# Controller.net
KiCad netlist of a schematic drawn in EAGLE
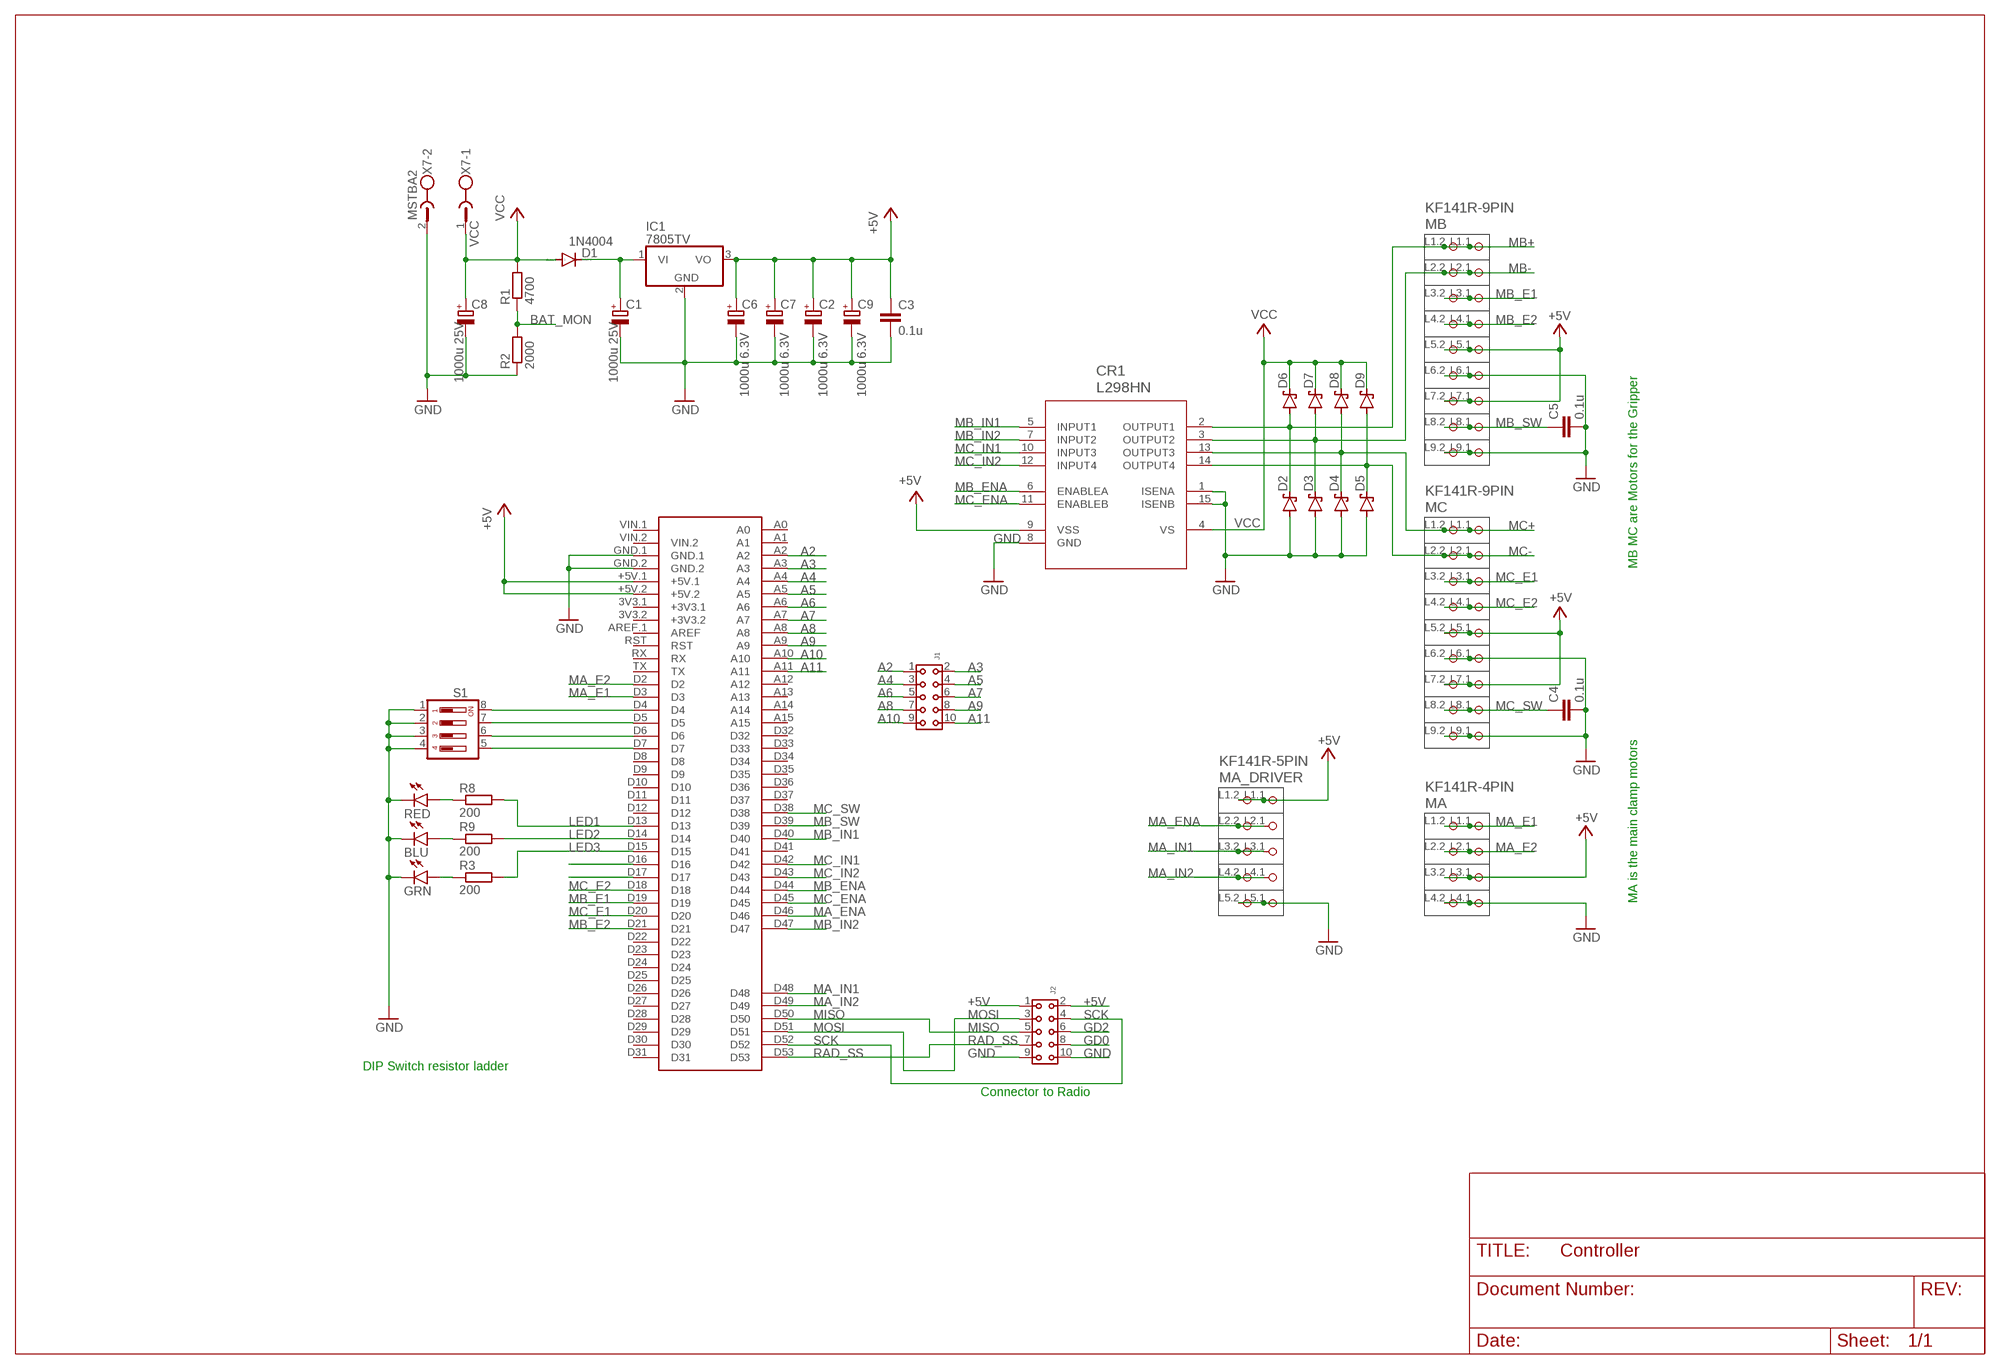
[diagram p0: schematic, sheet 1]

(export (version "E")
  (design (tool "Eeschema 10.0.6"))
  (components
    (comp (ref "BLU")
      (value "LED5MM")
      (footprint "eagle-import:LED5MM")
      (libsource (lib "eagle-import") (part "LED5MM"))
    )
    (comp (ref "C1")
      (value "1000u 25V")
      (footprint "eagle-import:E3,5-10")
      (libsource (lib "eagle-import") (part "resistor_348_CPOL-EUE3.5-10"))
    )
    (comp (ref "C2")
      (value "1000u 6.3V")
      (footprint "eagle-import:E4-8-13HORI")
      (libsource (lib "eagle-import") (part "CPOL-EU"))
    )
    (comp (ref "C3")
      (value "0.1u")
      (footprint "eagle-import:C050-030X075")
      (libsource (lib "eagle-import") (part "C-EU050-030X075"))
    )
    (comp (ref "C4")
      (value "0.1u")
      (footprint "eagle-import:C050-030X075")
      (libsource (lib "eagle-import") (part "C-EU050-030X075"))
    )
    (comp (ref "C5")
      (value "0.1u")
      (footprint "eagle-import:C050-030X075")
      (libsource (lib "eagle-import") (part "C-EU050-030X075"))
    )
    (comp (ref "C6")
      (value "1000u 6.3V")
      (footprint "eagle-import:E4-8-13HORI")
      (libsource (lib "eagle-import") (part "CPOL-EU"))
    )
    (comp (ref "C7")
      (value "1000u 6.3V")
      (footprint "eagle-import:E4-8-13HORI")
      (libsource (lib "eagle-import") (part "CPOL-EU"))
    )
    (comp (ref "C8")
      (value "1000u 25V")
      (footprint "eagle-import:E3,5-10")
      (libsource (lib "eagle-import") (part "resistor_348_CPOL-EUE3.5-10"))
    )
    (comp (ref "C9")
      (value "1000u 6.3V")
      (footprint "eagle-import:E4-8-13HORI")
      (libsource (lib "eagle-import") (part "CPOL-EU"))
    )
    (comp (ref "CR1")
      (value "L298HN")
      (footprint "eagle-import:MULTIWATT15_H_STM")
      (libsource (lib "eagle-import") (part "L298HN"))
    )
    (comp (ref "D1")
      (value "1N4004")
      (footprint "eagle-import:DO41-10")
      (libsource (lib "eagle-import") (part "1N4004"))
    )
    (comp (ref "D2")
      (value "1N5819-B")
      (footprint "eagle-import:DO41-7.6")
      (libsource (lib "eagle-import") (part "1N5819-B"))
    )
    (comp (ref "D3")
      (value "1N5819-B")
      (footprint "eagle-import:DO41-7.6")
      (libsource (lib "eagle-import") (part "1N5819-B"))
    )
    (comp (ref "D4")
      (value "1N5819-B")
      (footprint "eagle-import:DO41-7.6")
      (libsource (lib "eagle-import") (part "1N5819-B"))
    )
    (comp (ref "D5")
      (value "1N5819-B")
      (footprint "eagle-import:DO41-7.6")
      (libsource (lib "eagle-import") (part "1N5819-B"))
    )
    (comp (ref "D6")
      (value "1N5819-B")
      (footprint "eagle-import:DO41-7.6")
      (libsource (lib "eagle-import") (part "1N5819-B"))
    )
    (comp (ref "D7")
      (value "1N5819-B")
      (footprint "eagle-import:DO41-7.6")
      (libsource (lib "eagle-import") (part "1N5819-B"))
    )
    (comp (ref "D8")
      (value "1N5819-B")
      (footprint "eagle-import:DO41-7.6")
      (libsource (lib "eagle-import") (part "1N5819-B"))
    )
    (comp (ref "D9")
      (value "1N5819-B")
      (footprint "eagle-import:DO41-7.6")
      (libsource (lib "eagle-import") (part "1N5819-B"))
    )
    (comp (ref "GRN")
      (value "LED5MM")
      (footprint "eagle-import:LED5MM")
      (libsource (lib "eagle-import") (part "LED5MM"))
    )
    (comp (ref "IC1")
      (value "7805TV")
      (footprint "eagle-import:TO220V")
      (libsource (lib "eagle-import") (part "78TV05"))
    )
    (comp (ref "J1")
      (value "6130XX21821_61301021821")
      (footprint "eagle-import:61301021821")
      (libsource (lib "eagle-import") (part "6130XX21821_61301021821"))
    )
    (comp (ref "J2")
      (value "6130XX21821_61301021821")
      (footprint "eagle-import:61301021821")
      (libsource (lib "eagle-import") (part "6130XX21821_61301021821"))
    )
    (comp (ref "MA")
      (value "KF141R-4PIN")
      (footprint "eagle-import:KF141R-4PIN")
      (libsource (lib "eagle-import") (part "KF141R-4PIN"))
    )
    (comp (ref "MA_DRIVER")
      (value "KF141R-5PIN")
      (footprint "eagle-import:KF141R-5PIN")
      (libsource (lib "eagle-import") (part "KF141R-5PIN"))
    )
    (comp (ref "MB")
      (value "KF141R-9PIN")
      (footprint "eagle-import:KF141R-9PIN")
      (libsource (lib "eagle-import") (part "KF141R-9PIN"))
    )
    (comp (ref "MC")
      (value "KF141R-9PIN")
      (footprint "eagle-import:KF141R-9PIN")
      (libsource (lib "eagle-import") (part "KF141R-9PIN"))
    )
    (comp (ref "R1")
      (value "4700")
      (footprint "eagle-import:0207_7")
      (libsource (lib "eagle-import") (part "R-EU_0207/7"))
    )
    (comp (ref "R2")
      (value "2000")
      (footprint "eagle-import:0207_7")
      (libsource (lib "eagle-import") (part "R-EU_0207/7"))
    )
    (comp (ref "R3")
      (value "200")
      (footprint "eagle-import:0207_7")
      (libsource (lib "eagle-import") (part "R-EU_0207/7"))
    )
    (comp (ref "R8")
      (value "200")
      (footprint "eagle-import:0207_7")
      (libsource (lib "eagle-import") (part "R-EU_0207/7"))
    )
    (comp (ref "R9")
      (value "200")
      (footprint "eagle-import:0207_7")
      (libsource (lib "eagle-import") (part "R-EU_0207/7"))
    )
    (comp (ref "RED")
      (value "LED5MM")
      (footprint "eagle-import:LED5MM")
      (libsource (lib "eagle-import") (part "LED5MM"))
    )
    (comp (ref "S1")
      (value "DIP04YL")
      (footprint "eagle-import:DIP04YL")
      (libsource (lib "eagle-import") (part "DIP04YL"))
    )
    (comp (ref "U$1")
      (value "MEGA2560_MIKRO")
      (footprint "eagle-import:MEGA2560_MIKRO")
      (libsource (lib "eagle-import") (part "MEGA2560_MIKRO"))
    )
    (comp (ref "X7")
      (value "MSTBA2")
      (footprint "eagle-import:MSTBA2")
      (fields (field (name "MF") "FARNELL") (field (name "MPN") "1757242"))
      (libsource (lib "eagle-import") (part "MSTBA2"))
    )
  )
  (nets
    (net (code "1") (name "+5V") (class "Default")
      (node (ref "C2") (pin "+") (pinfunction "+_+") (pintype "passive"))
      (node (ref "C3") (pin "1") (pinfunction "1_1") (pintype "passive"))
      (node (ref "C6") (pin "+") (pinfunction "+_+") (pintype "passive"))
      (node (ref "C7") (pin "+") (pinfunction "+_+") (pintype "passive"))
      (node (ref "C9") (pin "+") (pinfunction "+_+") (pintype "passive"))
      (node (ref "CR1") (pin "9") (pinfunction "VSS_9") (pintype "power_in"))
      (node (ref "IC1") (pin "3") (pinfunction "VO_3") (pintype "passive"))
      (node (ref "J2") (pin "1") (pinfunction "1_1") (pintype "passive"))
      (node (ref "J2") (pin "2") (pinfunction "2_2") (pintype "passive"))
      (node (ref "MA") (pin "L3.1") (pinfunction "P3.1_L3.1") (pintype "bidirectional"))
      (node (ref "MA") (pin "L3.2") (pinfunction "P3.2_L3.2") (pintype "bidirectional"))
      (node (ref "MA_DRIVER") (pin "L1.1") (pinfunction "P1.1_L1.1") (pintype "bidirectional"))
      (node (ref "MA_DRIVER") (pin "L1.2") (pinfunction "P1.2_L1.2") (pintype "bidirectional"))
      (node (ref "MB") (pin "L5.1") (pinfunction "P5.1_L5.1") (pintype "bidirectional"))
      (node (ref "MB") (pin "L5.2") (pinfunction "P5.2_L5.2") (pintype "bidirectional"))
      (node (ref "MB") (pin "L7.1") (pinfunction "P7.1_L7.1") (pintype "bidirectional"))
      (node (ref "MB") (pin "L7.2") (pinfunction "P7.2_L7.2") (pintype "bidirectional"))
      (node (ref "MC") (pin "L5.1") (pinfunction "P5.1_L5.1") (pintype "bidirectional"))
      (node (ref "MC") (pin "L5.2") (pinfunction "P5.2_L5.2") (pintype "bidirectional"))
      (node (ref "MC") (pin "L7.1") (pinfunction "P7.1_L7.1") (pintype "bidirectional"))
      (node (ref "MC") (pin "L7.2") (pinfunction "P7.2_L7.2") (pintype "bidirectional"))
      (node (ref "U$1") (pin "+5V.1") (pinfunction "+5V.1_+5V.1") (pintype "bidirectional"))
      (node (ref "U$1") (pin "+5V.2") (pinfunction "+5V.2_+5V.2") (pintype "bidirectional"))
    )
    (net (code "2") (name "/A2") (class "Default")
      (node (ref "J1") (pin "1") (pinfunction "1_1") (pintype "passive"))
      (node (ref "U$1") (pin "A2") (pinfunction "A2_A2") (pintype "bidirectional"))
    )
    (net (code "3") (name "/A3") (class "Default")
      (node (ref "J1") (pin "2") (pinfunction "2_2") (pintype "passive"))
      (node (ref "U$1") (pin "A3") (pinfunction "A3_A3") (pintype "bidirectional"))
    )
    (net (code "4") (name "/A4") (class "Default")
      (node (ref "J1") (pin "3") (pinfunction "3_3") (pintype "passive"))
      (node (ref "U$1") (pin "A4") (pinfunction "A4_A4") (pintype "bidirectional"))
    )
    (net (code "5") (name "/A5") (class "Default")
      (node (ref "J1") (pin "4") (pinfunction "4_4") (pintype "passive"))
      (node (ref "U$1") (pin "A5") (pinfunction "A5_A5") (pintype "bidirectional"))
    )
    (net (code "6") (name "/A6") (class "Default")
      (node (ref "J1") (pin "5") (pinfunction "5_5") (pintype "passive"))
      (node (ref "U$1") (pin "A6") (pinfunction "A6_A6") (pintype "bidirectional"))
    )
    (net (code "7") (name "/A7") (class "Default")
      (node (ref "J1") (pin "6") (pinfunction "6_6") (pintype "passive"))
      (node (ref "U$1") (pin "A7") (pinfunction "A7_A7") (pintype "bidirectional"))
    )
    (net (code "8") (name "/A8") (class "Default")
      (node (ref "J1") (pin "7") (pinfunction "7_7") (pintype "passive"))
      (node (ref "U$1") (pin "A8") (pinfunction "A8_A8") (pintype "bidirectional"))
    )
    (net (code "9") (name "/A9") (class "Default")
      (node (ref "J1") (pin "8") (pinfunction "8_8") (pintype "passive"))
      (node (ref "U$1") (pin "A9") (pinfunction "A9_A9") (pintype "bidirectional"))
    )
    (net (code "10") (name "/A10") (class "Default")
      (node (ref "J1") (pin "9") (pinfunction "9_9") (pintype "passive"))
      (node (ref "U$1") (pin "A10") (pinfunction "A10_A10") (pintype "bidirectional"))
    )
    (net (code "11") (name "/A11") (class "Default")
      (node (ref "J1") (pin "10") (pinfunction "10_10") (pintype "passive"))
      (node (ref "U$1") (pin "A11") (pinfunction "A11_A11") (pintype "bidirectional"))
    )
    (net (code "12") (name "/BAT_MON") (class "Default")
      (node (ref "R1") (pin "1") (pinfunction "1_1") (pintype "passive"))
      (node (ref "R2") (pin "2") (pinfunction "2_2") (pintype "passive"))
    )
    (net (code "13") (name "/GD0") (class "Default")
      (node (ref "J2") (pin "8") (pinfunction "8_8") (pintype "passive"))
    )
    (net (code "14") (name "/GD2") (class "Default")
      (node (ref "J2") (pin "6") (pinfunction "6_6") (pintype "passive"))
    )
    (net (code "15") (name "/LED1") (class "Default")
      (node (ref "R8") (pin "2") (pinfunction "2_2") (pintype "passive"))
      (node (ref "U$1") (pin "D13") (pinfunction "D13_D13") (pintype "bidirectional"))
    )
    (net (code "16") (name "/LED2") (class "Default")
      (node (ref "R9") (pin "2") (pinfunction "2_2") (pintype "passive"))
      (node (ref "U$1") (pin "D14") (pinfunction "D14_D14") (pintype "bidirectional"))
    )
    (net (code "17") (name "/LED3") (class "Default")
      (node (ref "R3") (pin "2") (pinfunction "2_2") (pintype "passive"))
      (node (ref "U$1") (pin "D15") (pinfunction "D15_D15") (pintype "bidirectional"))
    )
    (net (code "18") (name "/MA_E1") (class "Default")
      (node (ref "MA") (pin "L1.1") (pinfunction "P1.1_L1.1") (pintype "bidirectional"))
      (node (ref "MA") (pin "L1.2") (pinfunction "P1.2_L1.2") (pintype "bidirectional"))
      (node (ref "U$1") (pin "D3") (pinfunction "D3_D3") (pintype "bidirectional"))
    )
    (net (code "19") (name "/MA_E2") (class "Default")
      (node (ref "MA") (pin "L2.1") (pinfunction "P2.1_L2.1") (pintype "bidirectional"))
      (node (ref "MA") (pin "L2.2") (pinfunction "P2.2_L2.2") (pintype "bidirectional"))
      (node (ref "U$1") (pin "D2") (pinfunction "D2_D2") (pintype "bidirectional"))
    )
    (net (code "20") (name "/MA_ENA") (class "Default")
      (node (ref "MA_DRIVER") (pin "L2.1") (pinfunction "P2.1_L2.1") (pintype "bidirectional"))
      (node (ref "MA_DRIVER") (pin "L2.2") (pinfunction "P2.2_L2.2") (pintype "bidirectional"))
      (node (ref "U$1") (pin "D46") (pinfunction "D46_D46") (pintype "bidirectional"))
    )
    (net (code "21") (name "/MA_IN1") (class "Default")
      (node (ref "MA_DRIVER") (pin "L3.1") (pinfunction "P3.1_L3.1") (pintype "bidirectional"))
      (node (ref "MA_DRIVER") (pin "L3.2") (pinfunction "P3.2_L3.2") (pintype "bidirectional"))
      (node (ref "U$1") (pin "D48") (pinfunction "D48_D48") (pintype "bidirectional"))
    )
    (net (code "22") (name "/MA_IN2") (class "Default")
      (node (ref "MA_DRIVER") (pin "L4.1") (pinfunction "P4.1_L4.1") (pintype "bidirectional"))
      (node (ref "MA_DRIVER") (pin "L4.2") (pinfunction "P4.2_L4.2") (pintype "bidirectional"))
      (node (ref "U$1") (pin "D49") (pinfunction "D49_D49") (pintype "bidirectional"))
    )
    (net (code "23") (name "/MB+") (class "Default")
      (node (ref "CR1") (pin "2") (pinfunction "OUTPUT1_2") (pintype "output"))
      (node (ref "D2") (pin "C") (pinfunction "C_C") (pintype "passive"))
      (node (ref "D6") (pin "A") (pinfunction "A_A") (pintype "passive"))
      (node (ref "MB") (pin "L1.1") (pinfunction "P1.1_L1.1") (pintype "bidirectional"))
      (node (ref "MB") (pin "L1.2") (pinfunction "P1.2_L1.2") (pintype "bidirectional"))
    )
    (net (code "24") (name "/MB-") (class "Default")
      (node (ref "CR1") (pin "3") (pinfunction "OUTPUT2_3") (pintype "output"))
      (node (ref "D3") (pin "C") (pinfunction "C_C") (pintype "passive"))
      (node (ref "D7") (pin "A") (pinfunction "A_A") (pintype "passive"))
      (node (ref "MB") (pin "L2.1") (pinfunction "P2.1_L2.1") (pintype "bidirectional"))
      (node (ref "MB") (pin "L2.2") (pinfunction "P2.2_L2.2") (pintype "bidirectional"))
    )
    (net (code "25") (name "/MB_E1") (class "Default")
      (node (ref "MB") (pin "L3.1") (pinfunction "P3.1_L3.1") (pintype "bidirectional"))
      (node (ref "MB") (pin "L3.2") (pinfunction "P3.2_L3.2") (pintype "bidirectional"))
      (node (ref "U$1") (pin "D19") (pinfunction "D19_D19") (pintype "bidirectional"))
    )
    (net (code "26") (name "/MB_E2") (class "Default")
      (node (ref "MB") (pin "L4.1") (pinfunction "P4.1_L4.1") (pintype "bidirectional"))
      (node (ref "MB") (pin "L4.2") (pinfunction "P4.2_L4.2") (pintype "bidirectional"))
      (node (ref "U$1") (pin "D21") (pinfunction "D21_D21") (pintype "bidirectional"))
    )
    (net (code "27") (name "/MB_ENA") (class "Default")
      (node (ref "CR1") (pin "6") (pinfunction "ENABLEA_6") (pintype "input"))
      (node (ref "U$1") (pin "D44") (pinfunction "D44_D44") (pintype "bidirectional"))
    )
    (net (code "28") (name "/MB_IN1") (class "Default")
      (node (ref "CR1") (pin "5") (pinfunction "INPUT1_5") (pintype "input"))
      (node (ref "U$1") (pin "D40") (pinfunction "D40_D40") (pintype "bidirectional"))
    )
    (net (code "29") (name "/MB_IN2") (class "Default")
      (node (ref "CR1") (pin "7") (pinfunction "INPUT2_7") (pintype "input"))
      (node (ref "U$1") (pin "D47") (pinfunction "D47_D47") (pintype "bidirectional"))
    )
    (net (code "30") (name "/MB_SW") (class "Default")
      (node (ref "C5") (pin "1") (pinfunction "1_1") (pintype "passive"))
      (node (ref "MB") (pin "L8.1") (pinfunction "P8.1_L8.1") (pintype "bidirectional"))
      (node (ref "MB") (pin "L8.2") (pinfunction "P8.2_L8.2") (pintype "bidirectional"))
      (node (ref "U$1") (pin "D39") (pinfunction "D39_D39") (pintype "bidirectional"))
    )
    (net (code "31") (name "/MC+") (class "Default")
      (node (ref "CR1") (pin "13") (pinfunction "OUTPUT3_13") (pintype "output"))
      (node (ref "D4") (pin "C") (pinfunction "C_C") (pintype "passive"))
      (node (ref "D8") (pin "A") (pinfunction "A_A") (pintype "passive"))
      (node (ref "MC") (pin "L1.1") (pinfunction "P1.1_L1.1") (pintype "bidirectional"))
      (node (ref "MC") (pin "L1.2") (pinfunction "P1.2_L1.2") (pintype "bidirectional"))
    )
    (net (code "32") (name "/MC-") (class "Default")
      (node (ref "CR1") (pin "14") (pinfunction "OUTPUT4_14") (pintype "output"))
      (node (ref "D5") (pin "C") (pinfunction "C_C") (pintype "passive"))
      (node (ref "D9") (pin "A") (pinfunction "A_A") (pintype "passive"))
      (node (ref "MC") (pin "L2.1") (pinfunction "P2.1_L2.1") (pintype "bidirectional"))
      (node (ref "MC") (pin "L2.2") (pinfunction "P2.2_L2.2") (pintype "bidirectional"))
    )
    (net (code "33") (name "/MC_E1") (class "Default")
      (node (ref "MC") (pin "L3.1") (pinfunction "P3.1_L3.1") (pintype "bidirectional"))
      (node (ref "MC") (pin "L3.2") (pinfunction "P3.2_L3.2") (pintype "bidirectional"))
      (node (ref "U$1") (pin "D20") (pinfunction "D20_D20") (pintype "bidirectional"))
    )
    (net (code "34") (name "/MC_E2") (class "Default")
      (node (ref "MC") (pin "L4.1") (pinfunction "P4.1_L4.1") (pintype "bidirectional"))
      (node (ref "MC") (pin "L4.2") (pinfunction "P4.2_L4.2") (pintype "bidirectional"))
      (node (ref "U$1") (pin "D18") (pinfunction "D18_D18") (pintype "bidirectional"))
    )
    (net (code "35") (name "/MC_ENA") (class "Default")
      (node (ref "CR1") (pin "11") (pinfunction "ENABLEB_11") (pintype "input"))
      (node (ref "U$1") (pin "D45") (pinfunction "D45_D45") (pintype "bidirectional"))
    )
    (net (code "36") (name "/MC_IN1") (class "Default")
      (node (ref "CR1") (pin "10") (pinfunction "INPUT3_10") (pintype "input"))
      (node (ref "U$1") (pin "D42") (pinfunction "D42_D42") (pintype "bidirectional"))
    )
    (net (code "37") (name "/MC_IN2") (class "Default")
      (node (ref "CR1") (pin "12") (pinfunction "INPUT4_12") (pintype "input"))
      (node (ref "U$1") (pin "D43") (pinfunction "D43_D43") (pintype "bidirectional"))
    )
    (net (code "38") (name "/MC_SW") (class "Default")
      (node (ref "C4") (pin "1") (pinfunction "1_1") (pintype "passive"))
      (node (ref "MC") (pin "L8.1") (pinfunction "P8.1_L8.1") (pintype "bidirectional"))
      (node (ref "MC") (pin "L8.2") (pinfunction "P8.2_L8.2") (pintype "bidirectional"))
      (node (ref "U$1") (pin "D38") (pinfunction "D38_D38") (pintype "bidirectional"))
    )
    (net (code "39") (name "/MISO") (class "Default")
      (node (ref "J2") (pin "5") (pinfunction "5_5") (pintype "passive"))
      (node (ref "U$1") (pin "D50") (pinfunction "D50_D50") (pintype "bidirectional"))
    )
    (net (code "40") (name "/MOSI") (class "Default")
      (node (ref "J2") (pin "3") (pinfunction "3_3") (pintype "passive"))
      (node (ref "U$1") (pin "D51") (pinfunction "D51_D51") (pintype "bidirectional"))
    )
    (net (code "41") (name "/RAD_SS") (class "Default")
      (node (ref "J2") (pin "7") (pinfunction "7_7") (pintype "passive"))
      (node (ref "U$1") (pin "D53") (pinfunction "D53_D53") (pintype "bidirectional"))
    )
    (net (code "42") (name "/SCK") (class "Default")
      (node (ref "J2") (pin "4") (pinfunction "4_4") (pintype "passive"))
      (node (ref "U$1") (pin "D52") (pinfunction "D52_D52") (pintype "bidirectional"))
    )
    (net (code "43") (name "GND") (class "Default")
      (node (ref "BLU") (pin "K") (pinfunction "C_K") (pintype "passive"))
      (node (ref "C1") (pin "-") (pinfunction "-_-") (pintype "passive"))
      (node (ref "C2") (pin "-") (pinfunction "-_-") (pintype "passive"))
      (node (ref "C3") (pin "2") (pinfunction "2_2") (pintype "passive"))
      (node (ref "C4") (pin "2") (pinfunction "2_2") (pintype "passive"))
      (node (ref "C5") (pin "2") (pinfunction "2_2") (pintype "passive"))
      (node (ref "C6") (pin "-") (pinfunction "-_-") (pintype "passive"))
      (node (ref "C7") (pin "-") (pinfunction "-_-") (pintype "passive"))
      (node (ref "C8") (pin "-") (pinfunction "-_-") (pintype "passive"))
      (node (ref "C9") (pin "-") (pinfunction "-_-") (pintype "passive"))
      (node (ref "CR1") (pin "1") (pinfunction "ISENA_1") (pintype "passive"))
      (node (ref "CR1") (pin "15") (pinfunction "ISENB_15") (pintype "passive"))
      (node (ref "CR1") (pin "8") (pinfunction "GND_8") (pintype "power_in"))
      (node (ref "D2") (pin "A") (pinfunction "A_A") (pintype "passive"))
      (node (ref "D3") (pin "A") (pinfunction "A_A") (pintype "passive"))
      (node (ref "D4") (pin "A") (pinfunction "A_A") (pintype "passive"))
      (node (ref "D5") (pin "A") (pinfunction "A_A") (pintype "passive"))
      (node (ref "GRN") (pin "K") (pinfunction "C_K") (pintype "passive"))
      (node (ref "IC1") (pin "2") (pinfunction "GND_2") (pintype "passive"))
      (node (ref "J2") (pin "10") (pinfunction "10_10") (pintype "passive"))
      (node (ref "J2") (pin "9") (pinfunction "9_9") (pintype "passive"))
      (node (ref "MA") (pin "L4.1") (pinfunction "P4.1_L4.1") (pintype "bidirectional"))
      (node (ref "MA") (pin "L4.2") (pinfunction "P4.2_L4.2") (pintype "bidirectional"))
      (node (ref "MA_DRIVER") (pin "L5.1") (pinfunction "P5.1_L5.1") (pintype "bidirectional"))
      (node (ref "MA_DRIVER") (pin "L5.2") (pinfunction "P5.2_L5.2") (pintype "bidirectional"))
      (node (ref "MB") (pin "L6.1") (pinfunction "P6.1_L6.1") (pintype "bidirectional"))
      (node (ref "MB") (pin "L6.2") (pinfunction "P6.2_L6.2") (pintype "bidirectional"))
      (node (ref "MB") (pin "L9.1") (pinfunction "P9.1_L9.1") (pintype "bidirectional"))
      (node (ref "MB") (pin "L9.2") (pinfunction "P9.2_L9.2") (pintype "bidirectional"))
      (node (ref "MC") (pin "L6.1") (pinfunction "P6.1_L6.1") (pintype "bidirectional"))
      (node (ref "MC") (pin "L6.2") (pinfunction "P6.2_L6.2") (pintype "bidirectional"))
      (node (ref "MC") (pin "L9.1") (pinfunction "P9.1_L9.1") (pintype "bidirectional"))
      (node (ref "MC") (pin "L9.2") (pinfunction "P9.2_L9.2") (pintype "bidirectional"))
      (node (ref "R2") (pin "1") (pinfunction "1_1") (pintype "passive"))
      (node (ref "RED") (pin "K") (pinfunction "C_K") (pintype "passive"))
      (node (ref "S1") (pin "1") (pinfunction "1_1") (pintype "passive"))
      (node (ref "S1") (pin "2") (pinfunction "2_2") (pintype "passive"))
      (node (ref "S1") (pin "3") (pinfunction "3_3") (pintype "passive"))
      (node (ref "S1") (pin "4") (pinfunction "4_4") (pintype "passive"))
      (node (ref "U$1") (pin "GND.1") (pinfunction "GND.1_GND.1") (pintype "bidirectional"))
      (node (ref "U$1") (pin "GND.2") (pinfunction "GND.2_GND.2") (pintype "bidirectional"))
      (node (ref "X7") (pin "2") (pinfunction "1_2") (pintype "passive"))
    )
    (net (code "44") (name "Net-(BLU-PadA)") (class "Default")
      (node (ref "BLU") (pin "A") (pinfunction "A_A") (pintype "passive"))
      (node (ref "R9") (pin "1") (pinfunction "1_1") (pintype "passive"))
    )
    (net (code "45") (name "Net-(GRN-PadA)") (class "Default")
      (node (ref "GRN") (pin "A") (pinfunction "A_A") (pintype "passive"))
      (node (ref "R3") (pin "1") (pinfunction "1_1") (pintype "passive"))
    )
    (net (code "46") (name "Net-(IC1-VI)") (class "Default")
      (node (ref "C1") (pin "+") (pinfunction "+_+") (pintype "passive"))
      (node (ref "D1") (pin "C") (pinfunction "C_C") (pintype "passive"))
      (node (ref "IC1") (pin "1") (pinfunction "VI_1") (pintype "input"))
    )
    (net (code "47") (name "Net-(R8-Pad1)") (class "Default")
      (node (ref "R8") (pin "1") (pinfunction "1_1") (pintype "passive"))
      (node (ref "RED") (pin "A") (pinfunction "A_A") (pintype "passive"))
    )
    (net (code "48") (name "Net-(S1-Pad5)") (class "Default")
      (node (ref "S1") (pin "5") (pinfunction "5_5") (pintype "passive"))
      (node (ref "U$1") (pin "D7") (pinfunction "D7_D7") (pintype "bidirectional"))
    )
    (net (code "49") (name "Net-(S1-Pad6)") (class "Default")
      (node (ref "S1") (pin "6") (pinfunction "6_6") (pintype "passive"))
      (node (ref "U$1") (pin "D6") (pinfunction "D6_D6") (pintype "bidirectional"))
    )
    (net (code "50") (name "Net-(S1-Pad7)") (class "Default")
      (node (ref "S1") (pin "7") (pinfunction "7_7") (pintype "passive"))
      (node (ref "U$1") (pin "D5") (pinfunction "D5_D5") (pintype "bidirectional"))
    )
    (net (code "51") (name "Net-(S1-Pad8)") (class "Default")
      (node (ref "S1") (pin "8") (pinfunction "8_8") (pintype "passive"))
      (node (ref "U$1") (pin "D4") (pinfunction "D4_D4") (pintype "bidirectional"))
    )
    (net (code "52") (name "VCC") (class "Default")
      (node (ref "C8") (pin "+") (pinfunction "+_+") (pintype "passive"))
      (node (ref "CR1") (pin "4") (pinfunction "VS_4") (pintype "power_in"))
      (node (ref "D1") (pin "A") (pinfunction "A_A") (pintype "passive"))
      (node (ref "D6") (pin "C") (pinfunction "C_C") (pintype "passive"))
      (node (ref "D7") (pin "C") (pinfunction "C_C") (pintype "passive"))
      (node (ref "D8") (pin "C") (pinfunction "C_C") (pintype "passive"))
      (node (ref "D9") (pin "C") (pinfunction "C_C") (pintype "passive"))
      (node (ref "R1") (pin "2") (pinfunction "2_2") (pintype "passive"))
      (node (ref "X7") (pin "1") (pinfunction "1_1") (pintype "passive"))
    )
    (net (code "53") (name "unconnected-(U$1-+3V3.1-Pad3V3.1)") (class "Default")
      (node (ref "U$1") (pin "3V3.1") (pinfunction "+3V3.1_3V3.1") (pintype "bidirectional"))
    )
    (net (code "54") (name "unconnected-(U$1-+3V3.2-Pad3V3.2)") (class "Default")
      (node (ref "U$1") (pin "3V3.2") (pinfunction "+3V3.2_3V3.2") (pintype "bidirectional"))
    )
    (net (code "55") (name "unconnected-(U$1-AREF-PadAREF.1)") (class "Default")
      (node (ref "U$1") (pin "AREF.1") (pinfunction "AREF_AREF.1") (pintype "bidirectional"))
    )
    (net (code "56") (name "unconnected-(U$1-PadA0)") (class "Default")
      (node (ref "U$1") (pin "A0") (pinfunction "A0_A0") (pintype "bidirectional"))
    )
    (net (code "57") (name "unconnected-(U$1-PadA1)") (class "Default")
      (node (ref "U$1") (pin "A1") (pinfunction "A1_A1") (pintype "bidirectional"))
    )
    (net (code "58") (name "unconnected-(U$1-PadA12)") (class "Default")
      (node (ref "U$1") (pin "A12") (pinfunction "A12_A12") (pintype "bidirectional"))
    )
    (net (code "59") (name "unconnected-(U$1-PadA13)") (class "Default")
      (node (ref "U$1") (pin "A13") (pinfunction "A13_A13") (pintype "bidirectional"))
    )
    (net (code "60") (name "unconnected-(U$1-PadA14)") (class "Default")
      (node (ref "U$1") (pin "A14") (pinfunction "A14_A14") (pintype "bidirectional"))
    )
    (net (code "61") (name "unconnected-(U$1-PadA15)") (class "Default")
      (node (ref "U$1") (pin "A15") (pinfunction "A15_A15") (pintype "bidirectional"))
    )
    (net (code "62") (name "unconnected-(U$1-PadD8)") (class "Default")
      (node (ref "U$1") (pin "D8") (pinfunction "D8_D8") (pintype "bidirectional"))
    )
    (net (code "63") (name "unconnected-(U$1-PadD9)") (class "Default")
      (node (ref "U$1") (pin "D9") (pinfunction "D9_D9") (pintype "bidirectional"))
    )
    (net (code "64") (name "unconnected-(U$1-PadD10)") (class "Default")
      (node (ref "U$1") (pin "D10") (pinfunction "D10_D10") (pintype "bidirectional"))
    )
    (net (code "65") (name "unconnected-(U$1-PadD11)") (class "Default")
      (node (ref "U$1") (pin "D11") (pinfunction "D11_D11") (pintype "bidirectional"))
    )
    (net (code "66") (name "unconnected-(U$1-PadD12)") (class "Default")
      (node (ref "U$1") (pin "D12") (pinfunction "D12_D12") (pintype "bidirectional"))
    )
    (net (code "67") (name "unconnected-(U$1-PadD16)") (class "Default")
      (node (ref "U$1") (pin "D16") (pinfunction "D16_D16") (pintype "bidirectional"))
    )
    (net (code "68") (name "unconnected-(U$1-PadD17)") (class "Default")
      (node (ref "U$1") (pin "D17") (pinfunction "D17_D17") (pintype "bidirectional"))
    )
    (net (code "69") (name "unconnected-(U$1-PadD22)") (class "Default")
      (node (ref "U$1") (pin "D22") (pinfunction "D22_D22") (pintype "bidirectional"))
    )
    (net (code "70") (name "unconnected-(U$1-PadD23)") (class "Default")
      (node (ref "U$1") (pin "D23") (pinfunction "D23_D23") (pintype "bidirectional"))
    )
    (net (code "71") (name "unconnected-(U$1-PadD24)") (class "Default")
      (node (ref "U$1") (pin "D24") (pinfunction "D24_D24") (pintype "bidirectional"))
    )
    (net (code "72") (name "unconnected-(U$1-PadD25)") (class "Default")
      (node (ref "U$1") (pin "D25") (pinfunction "D25_D25") (pintype "bidirectional"))
    )
    (net (code "73") (name "unconnected-(U$1-PadD26)") (class "Default")
      (node (ref "U$1") (pin "D26") (pinfunction "D26_D26") (pintype "bidirectional"))
    )
    (net (code "74") (name "unconnected-(U$1-PadD27)") (class "Default")
      (node (ref "U$1") (pin "D27") (pinfunction "D27_D27") (pintype "bidirectional"))
    )
    (net (code "75") (name "unconnected-(U$1-PadD28)") (class "Default")
      (node (ref "U$1") (pin "D28") (pinfunction "D28_D28") (pintype "bidirectional"))
    )
    (net (code "76") (name "unconnected-(U$1-PadD29)") (class "Default")
      (node (ref "U$1") (pin "D29") (pinfunction "D29_D29") (pintype "bidirectional"))
    )
    (net (code "77") (name "unconnected-(U$1-PadD30)") (class "Default")
      (node (ref "U$1") (pin "D30") (pinfunction "D30_D30") (pintype "bidirectional"))
    )
    (net (code "78") (name "unconnected-(U$1-PadD31)") (class "Default")
      (node (ref "U$1") (pin "D31") (pinfunction "D31_D31") (pintype "bidirectional"))
    )
    (net (code "79") (name "unconnected-(U$1-PadD32)") (class "Default")
      (node (ref "U$1") (pin "D32") (pinfunction "D32_D32") (pintype "bidirectional"))
    )
    (net (code "80") (name "unconnected-(U$1-PadD33)") (class "Default")
      (node (ref "U$1") (pin "D33") (pinfunction "D33_D33") (pintype "bidirectional"))
    )
    (net (code "81") (name "unconnected-(U$1-PadD34)") (class "Default")
      (node (ref "U$1") (pin "D34") (pinfunction "D34_D34") (pintype "bidirectional"))
    )
    (net (code "82") (name "unconnected-(U$1-PadD35)") (class "Default")
      (node (ref "U$1") (pin "D35") (pinfunction "D35_D35") (pintype "bidirectional"))
    )
    (net (code "83") (name "unconnected-(U$1-PadD36)") (class "Default")
      (node (ref "U$1") (pin "D36") (pinfunction "D36_D36") (pintype "bidirectional"))
    )
    (net (code "84") (name "unconnected-(U$1-PadD37)") (class "Default")
      (node (ref "U$1") (pin "D37") (pinfunction "D37_D37") (pintype "bidirectional"))
    )
    (net (code "85") (name "unconnected-(U$1-PadD41)") (class "Default")
      (node (ref "U$1") (pin "D41") (pinfunction "D41_D41") (pintype "bidirectional"))
    )
    (net (code "86") (name "unconnected-(U$1-PadRST)") (class "Default")
      (node (ref "U$1") (pin "RST") (pinfunction "RST_RST") (pintype "bidirectional"))
    )
    (net (code "87") (name "unconnected-(U$1-PadRX)") (class "Default")
      (node (ref "U$1") (pin "RX") (pinfunction "RX_RX") (pintype "bidirectional"))
    )
    (net (code "88") (name "unconnected-(U$1-PadTX)") (class "Default")
      (node (ref "U$1") (pin "TX") (pinfunction "TX_TX") (pintype "bidirectional"))
    )
    (net (code "89") (name "unconnected-(U$1-PadVIN.1)") (class "Default")
      (node (ref "U$1") (pin "VIN.1") (pinfunction "VIN.1_VIN.1") (pintype "bidirectional"))
    )
    (net (code "90") (name "unconnected-(U$1-PadVIN.2)") (class "Default")
      (node (ref "U$1") (pin "VIN.2") (pinfunction "VIN.2_VIN.2") (pintype "bidirectional"))
    )
  )
)
